# 03_Power_Switch.net
KiCad netlist of a schematic drawn in Altium Designer
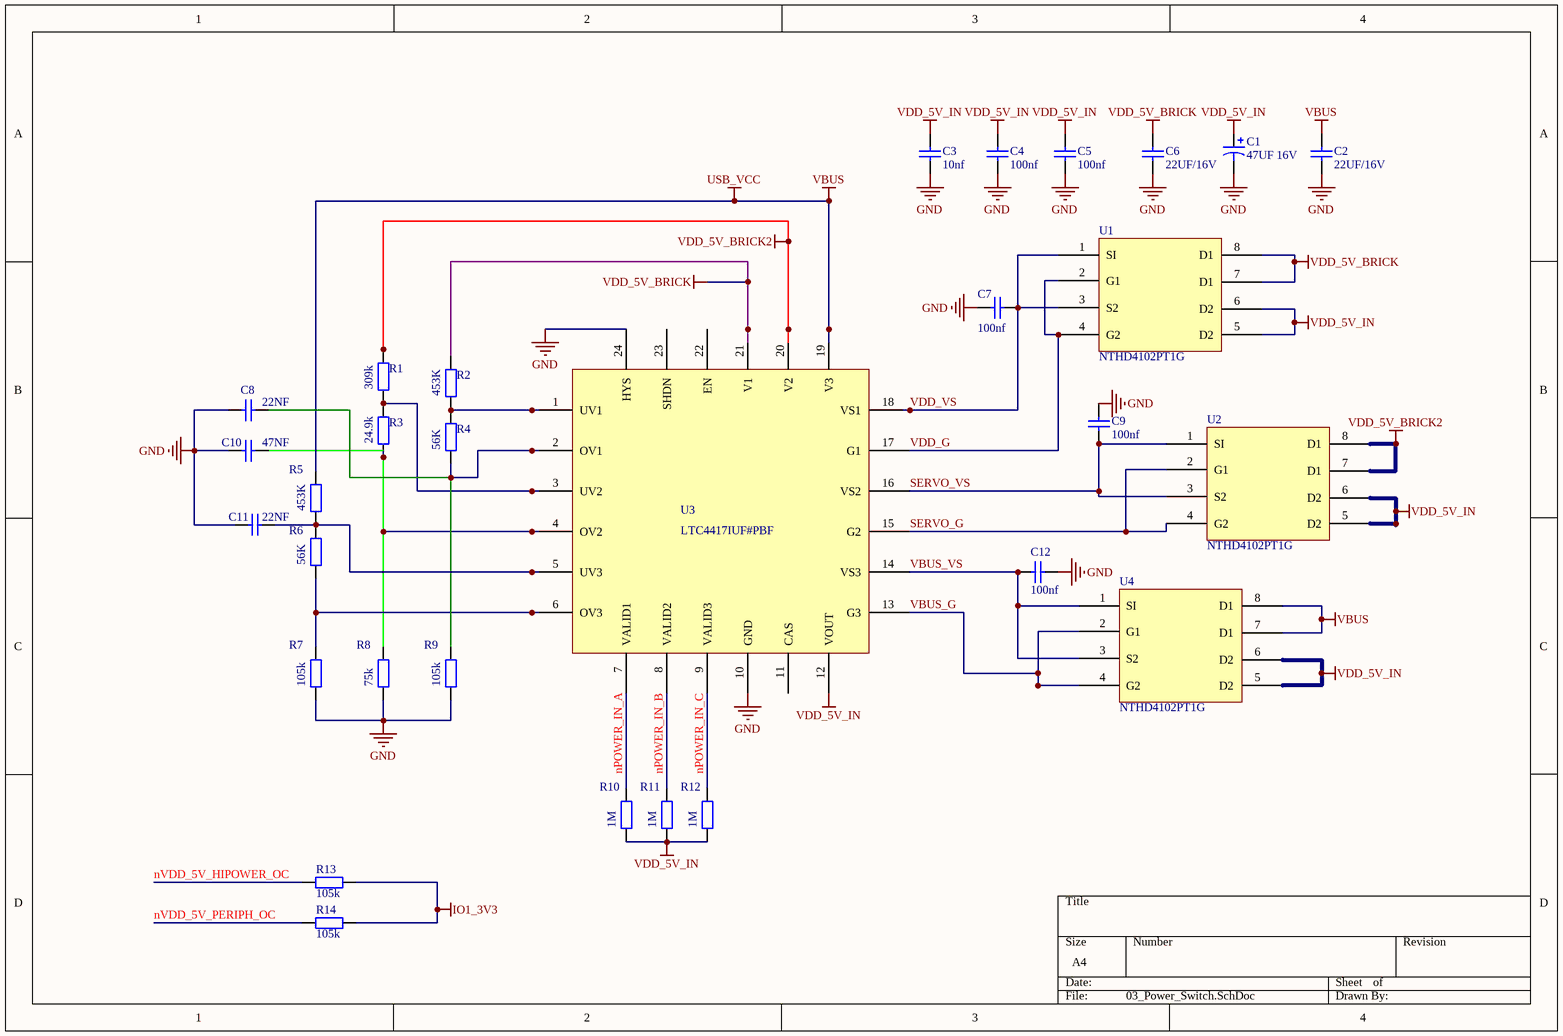
[diagram p0: 03_Power_Switch.SchDoc]

(export (version "E")
  (design (tool "Eeschema 10.0.6"))
  (components
    (comp (ref "C1")
      (value "47UF 16V")
      (footprint "7343CAP")
      (description "Polarized Capacitor (Radial)")
      (fields (field (name "PUBLISHER") "Altium Limited"))
      (libsource (lib "Miscellaneous Devices") (part "Cap Pol1"))
    )
    (comp (ref "C2")
      (value "22UF/16V")
      (fields (field (name "PUBLISHER") "Altium Limited"))
      (libsource (lib "Miscellaneous Devices") (part "Cap"))
    )
    (comp (ref "C3")
      (value "10nf")
      (fields (field (name "PUBLISHER") "Altium Limited"))
      (libsource (lib "Miscellaneous Devices") (part "Cap"))
    )
    (comp (ref "C4")
      (value "100nf")
      (fields (field (name "PUBLISHER") "Altium Limited"))
      (libsource (lib "Miscellaneous Devices") (part "Cap"))
    )
    (comp (ref "C5")
      (value "100nf")
      (fields (field (name "PUBLISHER") "Altium Limited"))
      (libsource (lib "Miscellaneous Devices") (part "Cap"))
    )
    (comp (ref "C6")
      (value "22UF/16V")
      (fields (field (name "PUBLISHER") "Altium Limited"))
      (libsource (lib "Miscellaneous Devices") (part "Cap"))
    )
    (comp (ref "C7")
      (value "100nf")
      (fields (field (name "PUBLISHER") "Altium Limited"))
      (libsource (lib "Miscellaneous Devices") (part "Cap"))
    )
    (comp (ref "C8")
      (value "22NF")
      (fields (field (name "PUBLISHER") "Altium Limited"))
      (libsource (lib "Miscellaneous Devices") (part "Cap"))
    )
    (comp (ref "C9")
      (value "100nf")
      (fields (field (name "PUBLISHER") "Altium Limited"))
      (libsource (lib "Miscellaneous Devices") (part "Cap"))
    )
    (comp (ref "C10")
      (value "47NF")
      (fields (field (name "PUBLISHER") "Altium Limited"))
      (libsource (lib "Miscellaneous Devices") (part "Cap"))
    )
    (comp (ref "C11")
      (value "22NF")
      (fields (field (name "PUBLISHER") "Altium Limited"))
      (libsource (lib "Miscellaneous Devices") (part "Cap"))
    )
    (comp (ref "C12")
      (value "100nf")
      (fields (field (name "PUBLISHER") "Altium Limited"))
      (libsource (lib "Miscellaneous Devices") (part "Cap"))
    )
    (comp (ref "R1")
      (value "309k")
      (description "Resistor")
      (fields (field (name "PUBLISHER") "Altium Limited"))
      (libsource (lib "Miscellaneous Devices") (part "Res2"))
    )
    (comp (ref "R2")
      (value "453K")
      (description "Resistor")
      (fields (field (name "PUBLISHER") "Altium Limited"))
      (libsource (lib "Miscellaneous Devices") (part "Res2"))
    )
    (comp (ref "R3")
      (value "24.9k")
      (description "Resistor")
      (fields (field (name "PUBLISHER") "Altium Limited"))
      (libsource (lib "Miscellaneous Devices") (part "Res2"))
    )
    (comp (ref "R4")
      (value "56K")
      (description "Resistor")
      (fields (field (name "PUBLISHER") "Altium Limited"))
      (libsource (lib "Miscellaneous Devices") (part "Res2"))
    )
    (comp (ref "R5")
      (value "453K")
      (description "Resistor")
      (fields (field (name "PUBLISHER") "Altium Limited"))
      (libsource (lib "Miscellaneous Devices") (part "Res2"))
    )
    (comp (ref "R6")
      (value "56K")
      (description "Resistor")
      (fields (field (name "PUBLISHER") "Altium Limited"))
      (libsource (lib "Miscellaneous Devices") (part "Res2"))
    )
    (comp (ref "R7")
      (value "105k")
      (description "Resistor")
      (fields (field (name "PUBLISHER") "Altium Limited"))
      (libsource (lib "Miscellaneous Devices") (part "Res2"))
    )
    (comp (ref "R8")
      (value "75k")
      (description "Resistor")
      (fields (field (name "PUBLISHER") "Altium Limited"))
      (libsource (lib "Miscellaneous Devices") (part "Res2"))
    )
    (comp (ref "R9")
      (value "105k")
      (description "Resistor")
      (fields (field (name "PUBLISHER") "Altium Limited"))
      (libsource (lib "Miscellaneous Devices") (part "Res2"))
    )
    (comp (ref "R10")
      (value "1M")
      (description "Resistor")
      (fields (field (name "PUBLISHER") "Altium Limited"))
      (libsource (lib "Miscellaneous Devices") (part "Res2"))
    )
    (comp (ref "R11")
      (value "1M")
      (description "Resistor")
      (fields (field (name "PUBLISHER") "Altium Limited"))
      (libsource (lib "Miscellaneous Devices") (part "Res2"))
    )
    (comp (ref "R12")
      (value "1M")
      (description "Resistor")
      (fields (field (name "PUBLISHER") "Altium Limited"))
      (libsource (lib "Miscellaneous Devices") (part "Res2"))
    )
    (comp (ref "R13")
      (value "105k")
      (description "Resistor")
      (fields (field (name "PUBLISHER") "Altium Limited"))
      (libsource (lib "") (part "Res2_1"))
    )
    (comp (ref "R14")
      (value "105k")
      (description "Resistor")
      (fields (field (name "PUBLISHER") "Altium Limited"))
      (libsource (lib "") (part "Res2_1"))
    )
    (comp (ref "U1")
      (value "NTHD4102PT1G")
      (footprint "1206-8")
      (libsource (lib "hack") (part "NTHD4102PT1G"))
    )
    (comp (ref "U2")
      (value "NTHD4102PT1G")
      (footprint "1206-8")
      (libsource (lib "hack") (part "NTHD4102PT1G"))
    )
    (comp (ref "U3")
      (value "LTC4417IUF#PBF")
      (footprint "QFN24")
      (libsource (lib "hack") (part "LTC4417IUF#PBF"))
    )
    (comp (ref "U4")
      (value "NTHD4102PT1G")
      (footprint "1206-8")
      (libsource (lib "hack") (part "NTHD4102PT1G"))
    )
  )
  (nets
    (net (code "1") (name "/SERVO_G") (class "Default")
      (node (ref "U2") (pin "2") (pinfunction "G1_2") (pintype "passive"))
      (node (ref "U2") (pin "4") (pinfunction "G2_4") (pintype "passive"))
      (node (ref "U3") (pin "15") (pinfunction "G2_15") (pintype "passive"))
    )
    (net (code "2") (name "/SERVO_VS") (class "Default")
      (node (ref "C9") (pin "1") (pinfunction "1_1") (pintype "passive"))
      (node (ref "U2") (pin "1") (pinfunction "SI_1") (pintype "passive"))
      (node (ref "U2") (pin "3") (pinfunction "S2_3") (pintype "passive"))
      (node (ref "U3") (pin "16") (pinfunction "VS2_16") (pintype "passive"))
    )
    (net (code "3") (name "/VBUS_G") (class "Default")
      (node (ref "U3") (pin "13") (pinfunction "G3_13") (pintype "passive"))
      (node (ref "U4") (pin "2") (pinfunction "G1_2") (pintype "passive"))
      (node (ref "U4") (pin "4") (pinfunction "G2_4") (pintype "passive"))
    )
    (net (code "4") (name "/VBUS_VS") (class "Default")
      (node (ref "C12") (pin "1") (pinfunction "1_1") (pintype "passive"))
      (node (ref "U3") (pin "14") (pinfunction "VS3_14") (pintype "passive"))
      (node (ref "U4") (pin "1") (pinfunction "SI_1") (pintype "passive"))
      (node (ref "U4") (pin "3") (pinfunction "S2_3") (pintype "passive"))
    )
    (net (code "5") (name "/VDD_G") (class "Default")
      (node (ref "U1") (pin "2") (pinfunction "G1_2") (pintype "passive"))
      (node (ref "U1") (pin "4") (pinfunction "G2_4") (pintype "passive"))
      (node (ref "U3") (pin "17") (pinfunction "G1_17") (pintype "passive"))
    )
    (net (code "6") (name "/VDD_VS") (class "Default")
      (node (ref "C7") (pin "1") (pinfunction "1_1") (pintype "passive"))
      (node (ref "U1") (pin "1") (pinfunction "SI_1") (pintype "passive"))
      (node (ref "U1") (pin "3") (pinfunction "S2_3") (pintype "passive"))
      (node (ref "U3") (pin "18") (pinfunction "VS1_18") (pintype "passive"))
    )
    (net (code "7") (name "/nPOWER_IN_A") (class "Default")
      (node (ref "R10") (pin "2") (pinfunction "2_2") (pintype "passive"))
      (node (ref "U3") (pin "7") (pinfunction "VALID1_7") (pintype "passive"))
    )
    (net (code "8") (name "/nPOWER_IN_B") (class "Default")
      (node (ref "R11") (pin "2") (pinfunction "2_2") (pintype "passive"))
      (node (ref "U3") (pin "8") (pinfunction "VALID2_8") (pintype "passive"))
    )
    (net (code "9") (name "/nPOWER_IN_C") (class "Default")
      (node (ref "R12") (pin "2") (pinfunction "2_2") (pintype "passive"))
      (node (ref "U3") (pin "9") (pinfunction "VALID3_9") (pintype "passive"))
    )
    (net (code "10") (name "/nVDD_5V_HIPOWER_OC") (class "Default")
      (node (ref "R13") (pin "1") (pinfunction "1_1") (pintype "passive"))
    )
    (net (code "11") (name "/nVDD_5V_PERIPH_OC") (class "Default")
      (node (ref "R14") (pin "1") (pinfunction "1_1") (pintype "passive"))
    )
    (net (code "12") (name "GND") (class "Default")
      (node (ref "C1") (pin "C") (pinfunction "2_C") (pintype "passive"))
      (node (ref "C10") (pin "2") (pinfunction "2_2") (pintype "passive"))
      (node (ref "C11") (pin "2") (pinfunction "2_2") (pintype "passive"))
      (node (ref "C12") (pin "2") (pinfunction "2_2") (pintype "passive"))
      (node (ref "C2") (pin "1") (pinfunction "1_1") (pintype "passive"))
      (node (ref "C3") (pin "1") (pinfunction "1_1") (pintype "passive"))
      (node (ref "C4") (pin "1") (pinfunction "1_1") (pintype "passive"))
      (node (ref "C5") (pin "1") (pinfunction "1_1") (pintype "passive"))
      (node (ref "C6") (pin "1") (pinfunction "1_1") (pintype "passive"))
      (node (ref "C7") (pin "2") (pinfunction "2_2") (pintype "passive"))
      (node (ref "C8") (pin "2") (pinfunction "2_2") (pintype "passive"))
      (node (ref "C9") (pin "2") (pinfunction "2_2") (pintype "passive"))
      (node (ref "R7") (pin "1") (pinfunction "1_1") (pintype "passive"))
      (node (ref "R8") (pin "1") (pinfunction "1_1") (pintype "passive"))
      (node (ref "R9") (pin "1") (pinfunction "1_1") (pintype "passive"))
      (node (ref "U3") (pin "10") (pinfunction "GND_10") (pintype "passive"))
      (node (ref "U3") (pin "24") (pinfunction "HYS_24") (pintype "passive"))
    )
    (net (code "13") (name "IO1_3V3") (class "Default")
      (node (ref "R13") (pin "2") (pinfunction "2_2") (pintype "passive"))
      (node (ref "R14") (pin "2") (pinfunction "2_2") (pintype "passive"))
    )
    (net (code "14") (name "Net-(U3-OV1)") (class "Default")
      (node (ref "C8") (pin "1") (pinfunction "1_1") (pintype "passive"))
      (node (ref "R4") (pin "1") (pinfunction "1_1") (pintype "passive"))
      (node (ref "R9") (pin "2") (pinfunction "2_2") (pintype "passive"))
      (node (ref "U3") (pin "2") (pinfunction "OV1_2") (pintype "passive"))
    )
    (net (code "15") (name "Net-(U3-OV2)") (class "Default")
      (node (ref "C10") (pin "1") (pinfunction "1_1") (pintype "passive"))
      (node (ref "R3") (pin "1") (pinfunction "1_1") (pintype "passive"))
      (node (ref "R8") (pin "2") (pinfunction "2_2") (pintype "passive"))
      (node (ref "U3") (pin "4") (pinfunction "OV2_4") (pintype "passive"))
    )
    (net (code "16") (name "Net-(U3-OV3)") (class "Default")
      (node (ref "R6") (pin "1") (pinfunction "1_1") (pintype "passive"))
      (node (ref "R7") (pin "2") (pinfunction "2_2") (pintype "passive"))
      (node (ref "U3") (pin "6") (pinfunction "OV3_6") (pintype "passive"))
    )
    (net (code "17") (name "Net-(U3-UV1)") (class "Default")
      (node (ref "R2") (pin "1") (pinfunction "1_1") (pintype "passive"))
      (node (ref "R4") (pin "2") (pinfunction "2_2") (pintype "passive"))
      (node (ref "U3") (pin "1") (pinfunction "UV1_1") (pintype "passive"))
    )
    (net (code "18") (name "Net-(U3-UV2)") (class "Default")
      (node (ref "R1") (pin "1") (pinfunction "1_1") (pintype "passive"))
      (node (ref "R3") (pin "2") (pinfunction "2_2") (pintype "passive"))
      (node (ref "U3") (pin "3") (pinfunction "UV2_3") (pintype "passive"))
    )
    (net (code "19") (name "Net-(U3-UV3)") (class "Default")
      (node (ref "C11") (pin "1") (pinfunction "1_1") (pintype "passive"))
      (node (ref "R5") (pin "1") (pinfunction "1_1") (pintype "passive"))
      (node (ref "R6") (pin "2") (pinfunction "2_2") (pintype "passive"))
      (node (ref "U3") (pin "5") (pinfunction "UV3_5") (pintype "passive"))
    )
    (net (code "20") (name "USB_VCC") (class "Default")
      (node (ref "C2") (pin "2") (pinfunction "2_2") (pintype "passive"))
      (node (ref "R5") (pin "2") (pinfunction "2_2") (pintype "passive"))
      (node (ref "U3") (pin "19") (pinfunction "V3_19") (pintype "passive"))
      (node (ref "U4") (pin "7") (pinfunction "D1_7") (pintype "passive"))
      (node (ref "U4") (pin "8") (pinfunction "D1_8") (pintype "passive"))
    )
    (net (code "21") (name "VDD_5V_BRICK") (class "Default")
      (node (ref "C6") (pin "2") (pinfunction "2_2") (pintype "passive"))
      (node (ref "R2") (pin "2") (pinfunction "2_2") (pintype "passive"))
      (node (ref "U1") (pin "7") (pinfunction "D1_7") (pintype "passive"))
      (node (ref "U1") (pin "8") (pinfunction "D1_8") (pintype "passive"))
      (node (ref "U3") (pin "21") (pinfunction "V1_21") (pintype "passive"))
    )
    (net (code "22") (name "VDD_5V_BRICK2") (class "Default")
      (node (ref "R1") (pin "2") (pinfunction "2_2") (pintype "passive"))
      (node (ref "U2") (pin "7") (pinfunction "D1_7") (pintype "passive"))
      (node (ref "U2") (pin "8") (pinfunction "D1_8") (pintype "passive"))
      (node (ref "U3") (pin "20") (pinfunction "V2_20") (pintype "passive"))
    )
    (net (code "23") (name "VDD_5V_IN") (class "Default")
      (node (ref "C1") (pin "A") (pinfunction "1_A") (pintype "passive"))
      (node (ref "C3") (pin "2") (pinfunction "2_2") (pintype "passive"))
      (node (ref "C4") (pin "2") (pinfunction "2_2") (pintype "passive"))
      (node (ref "C5") (pin "2") (pinfunction "2_2") (pintype "passive"))
      (node (ref "R10") (pin "1") (pinfunction "1_1") (pintype "passive"))
      (node (ref "R11") (pin "1") (pinfunction "1_1") (pintype "passive"))
      (node (ref "R12") (pin "1") (pinfunction "1_1") (pintype "passive"))
      (node (ref "U1") (pin "5") (pinfunction "D2_5") (pintype "passive"))
      (node (ref "U1") (pin "6") (pinfunction "D2_6") (pintype "passive"))
      (node (ref "U2") (pin "5") (pinfunction "D2_5") (pintype "passive"))
      (node (ref "U2") (pin "6") (pinfunction "D2_6") (pintype "passive"))
      (node (ref "U3") (pin "12") (pinfunction "VOUT_12") (pintype "passive"))
      (node (ref "U4") (pin "5") (pinfunction "D2_5") (pintype "passive"))
      (node (ref "U4") (pin "6") (pinfunction "D2_6") (pintype "passive"))
    )
    (net (code "24") (name "unconnected-(U3-CAS-Pad11)") (class "Default")
      (node (ref "U3") (pin "11") (pinfunction "CAS_11") (pintype "passive"))
    )
    (net (code "25") (name "unconnected-(U3-EN-Pad22)") (class "Default")
      (node (ref "U3") (pin "22") (pinfunction "EN_22") (pintype "passive"))
    )
    (net (code "26") (name "unconnected-(U3-SHDN-Pad23)") (class "Default")
      (node (ref "U3") (pin "23") (pinfunction "SHDN_23") (pintype "passive"))
    )
  )
)
